# NeoSevenSegment.net
KiCad netlist of a schematic drawn in EAGLE
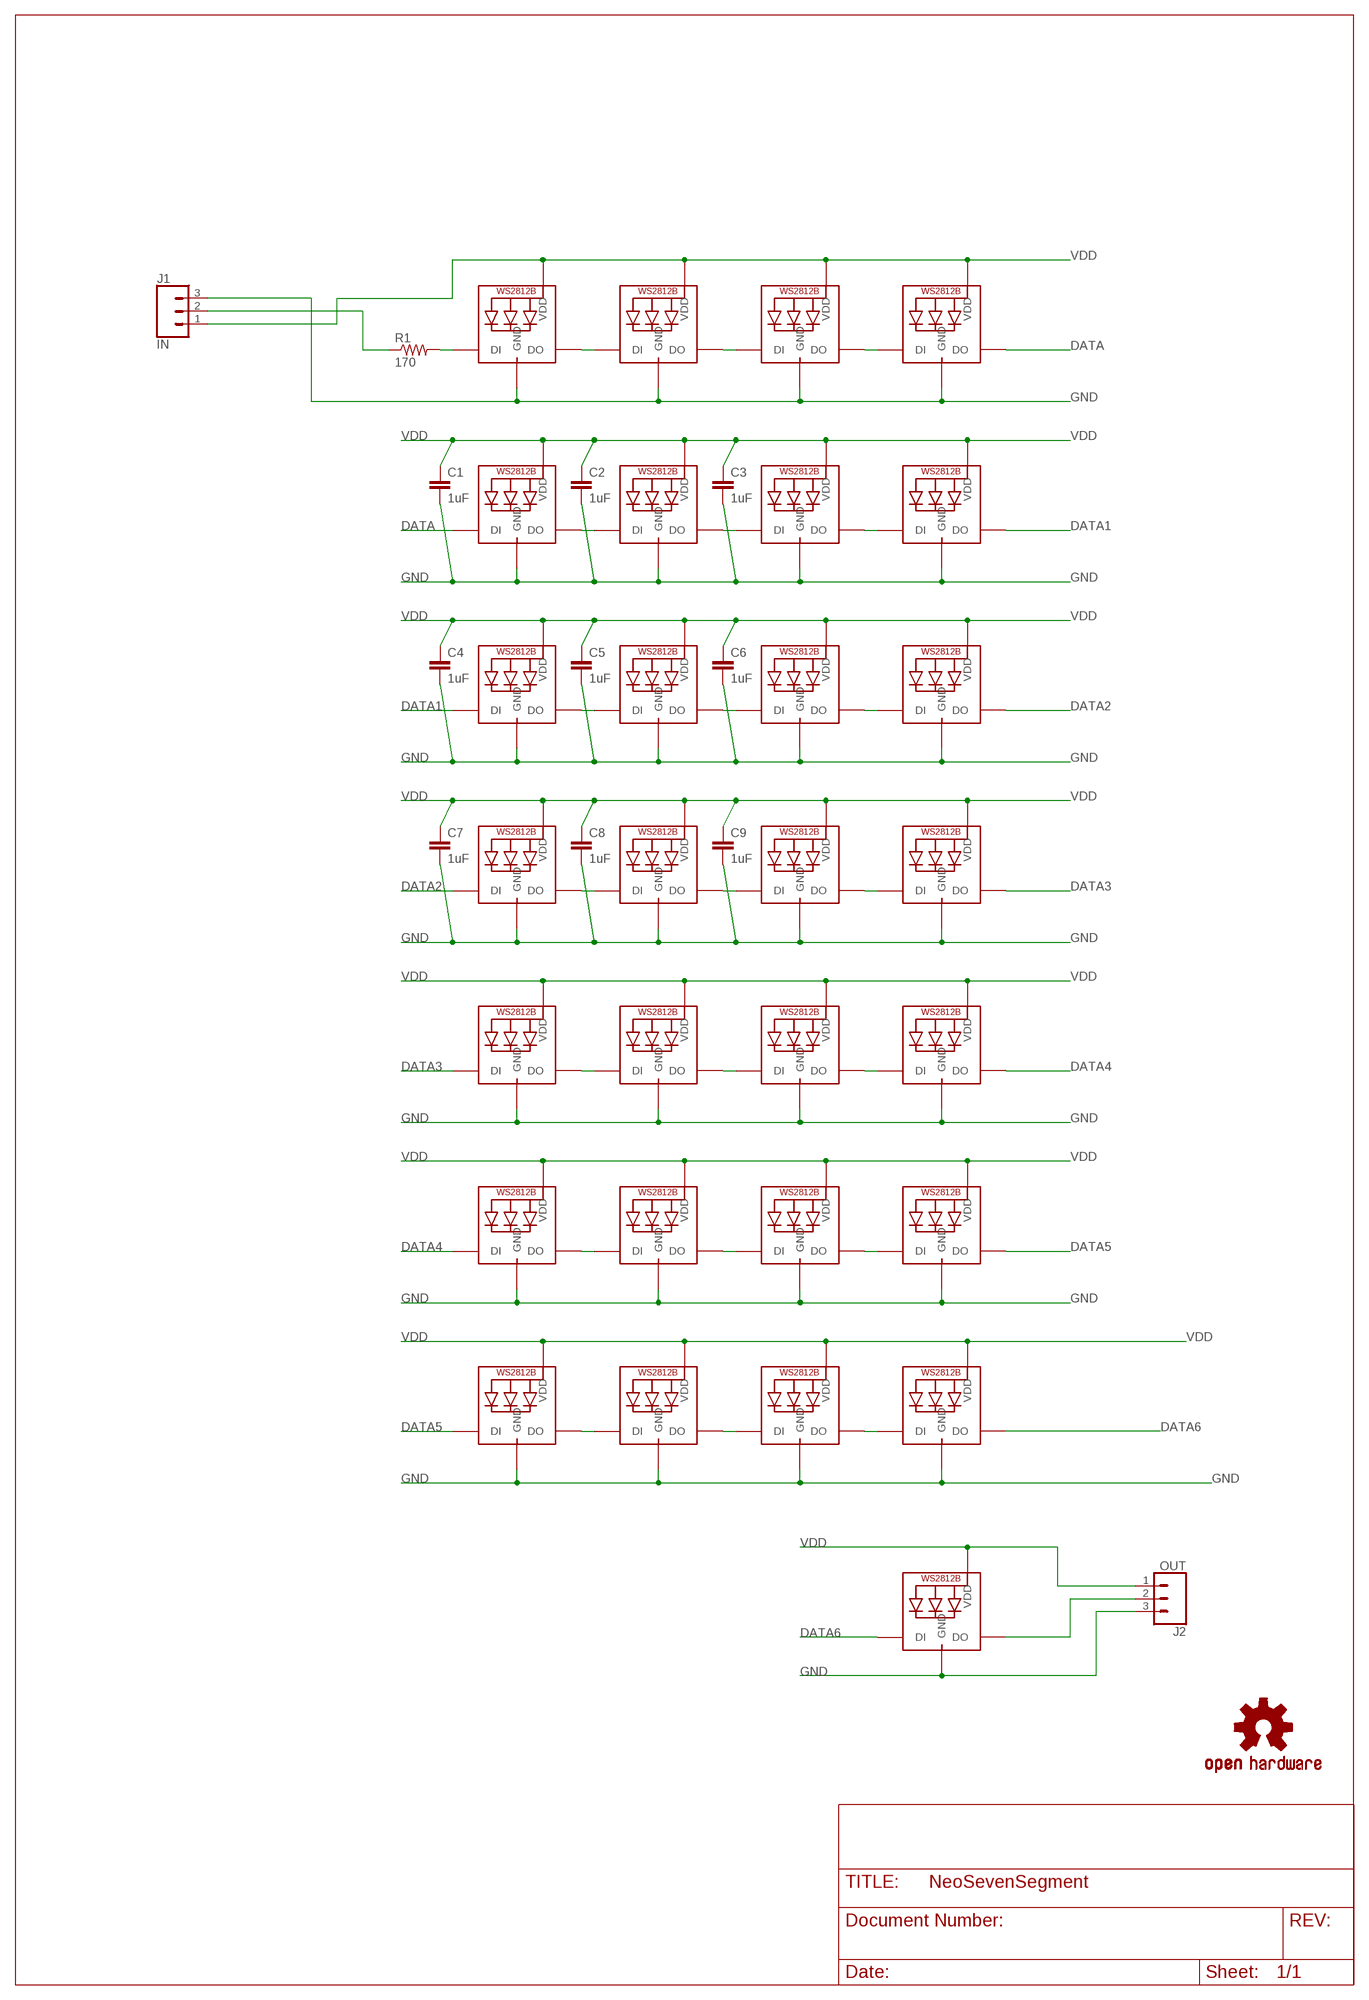
[diagram p0: schematic, sheet 1]

(export (version "E")
  (design (tool "Eeschema 10.0.6"))
  (components
    (comp (ref "C1")
      (value "1uF")
      (footprint "eagle-import:C0805")
      (libsource (lib "eagle-import") (part "C-EUC0805"))
    )
    (comp (ref "C2")
      (value "1uF")
      (footprint "eagle-import:C0805")
      (libsource (lib "eagle-import") (part "C-EUC0805"))
    )
    (comp (ref "C3")
      (value "1uF")
      (footprint "eagle-import:C0805")
      (libsource (lib "eagle-import") (part "C-EUC0805"))
    )
    (comp (ref "C4")
      (value "1uF")
      (footprint "eagle-import:C0805")
      (libsource (lib "eagle-import") (part "C-EUC0805"))
    )
    (comp (ref "C5")
      (value "1uF")
      (footprint "eagle-import:C0805")
      (libsource (lib "eagle-import") (part "C-EUC0805"))
    )
    (comp (ref "C6")
      (value "1uF")
      (footprint "eagle-import:C0805")
      (libsource (lib "eagle-import") (part "C-EUC0805"))
    )
    (comp (ref "C7")
      (value "1uF")
      (footprint "eagle-import:C0805")
      (libsource (lib "eagle-import") (part "C-EUC0805"))
    )
    (comp (ref "C8")
      (value "1uF")
      (footprint "eagle-import:C0805")
      (libsource (lib "eagle-import") (part "C-EUC0805"))
    )
    (comp (ref "C9")
      (value "1uF")
      (footprint "eagle-import:C0805")
      (libsource (lib "eagle-import") (part "C-EUC0805"))
    )
    (comp (ref "J1")
      (value "IN")
      (footprint "eagle-import:1X03_LONGPADS")
      (libsource (lib "eagle-import") (part "CONN_03LONGPADS"))
    )
    (comp (ref "J2")
      (value "OUT")
      (footprint "eagle-import:1X03_LONGPADS")
      (libsource (lib "eagle-import") (part "CONN_03LONGPADS"))
    )
    (comp (ref "LED1")
      (value "WS2812B_5050N")
      (footprint "eagle-import:WS2812B-NARROW")
      (libsource (lib "eagle-import") (part "WS2812B_5050N"))
    )
    (comp (ref "LED2")
      (value "WS2812B_5050N")
      (footprint "eagle-import:WS2812B-NARROW")
      (libsource (lib "eagle-import") (part "WS2812B_5050N"))
    )
    (comp (ref "LED3")
      (value "WS2812B_5050N")
      (footprint "eagle-import:WS2812B-NARROW")
      (libsource (lib "eagle-import") (part "WS2812B_5050N"))
    )
    (comp (ref "LED4")
      (value "WS2812B_5050N")
      (footprint "eagle-import:WS2812B-NARROW")
      (libsource (lib "eagle-import") (part "WS2812B_5050N"))
    )
    (comp (ref "LED5")
      (value "WS2812B_5050N")
      (footprint "eagle-import:WS2812B-NARROW")
      (libsource (lib "eagle-import") (part "WS2812B_5050N"))
    )
    (comp (ref "LED6")
      (value "WS2812B_5050N")
      (footprint "eagle-import:WS2812B-NARROW")
      (libsource (lib "eagle-import") (part "WS2812B_5050N"))
    )
    (comp (ref "LED7")
      (value "WS2812B_5050N")
      (footprint "eagle-import:WS2812B-NARROW")
      (libsource (lib "eagle-import") (part "WS2812B_5050N"))
    )
    (comp (ref "LED8")
      (value "WS2812B_5050N")
      (footprint "eagle-import:WS2812B-NARROW")
      (libsource (lib "eagle-import") (part "WS2812B_5050N"))
    )
    (comp (ref "LED9")
      (value "WS2812B_5050N")
      (footprint "eagle-import:WS2812B-NARROW")
      (libsource (lib "eagle-import") (part "WS2812B_5050N"))
    )
    (comp (ref "LED10")
      (value "WS2812B_5050N")
      (footprint "eagle-import:WS2812B-NARROW")
      (libsource (lib "eagle-import") (part "WS2812B_5050N"))
    )
    (comp (ref "LED11")
      (value "WS2812B_5050N")
      (footprint "eagle-import:WS2812B-NARROW")
      (libsource (lib "eagle-import") (part "WS2812B_5050N"))
    )
    (comp (ref "LED12")
      (value "WS2812B_5050N")
      (footprint "eagle-import:WS2812B-NARROW")
      (libsource (lib "eagle-import") (part "WS2812B_5050N"))
    )
    (comp (ref "LED13")
      (value "WS2812B_5050N")
      (footprint "eagle-import:WS2812B-NARROW")
      (libsource (lib "eagle-import") (part "WS2812B_5050N"))
    )
    (comp (ref "LED14")
      (value "WS2812B_5050N")
      (footprint "eagle-import:WS2812B-NARROW")
      (libsource (lib "eagle-import") (part "WS2812B_5050N"))
    )
    (comp (ref "LED15")
      (value "WS2812B_5050N")
      (footprint "eagle-import:WS2812B-NARROW")
      (libsource (lib "eagle-import") (part "WS2812B_5050N"))
    )
    (comp (ref "LED16")
      (value "WS2812B_5050N")
      (footprint "eagle-import:WS2812B-NARROW")
      (libsource (lib "eagle-import") (part "WS2812B_5050N"))
    )
    (comp (ref "LED17")
      (value "WS2812B_5050N")
      (footprint "eagle-import:WS2812B-NARROW")
      (libsource (lib "eagle-import") (part "WS2812B_5050N"))
    )
    (comp (ref "LED18")
      (value "WS2812B_5050N")
      (footprint "eagle-import:WS2812B-NARROW")
      (libsource (lib "eagle-import") (part "WS2812B_5050N"))
    )
    (comp (ref "LED19")
      (value "WS2812B_5050N")
      (footprint "eagle-import:WS2812B-NARROW")
      (libsource (lib "eagle-import") (part "WS2812B_5050N"))
    )
    (comp (ref "LED20")
      (value "WS2812B_5050N")
      (footprint "eagle-import:WS2812B-NARROW")
      (libsource (lib "eagle-import") (part "WS2812B_5050N"))
    )
    (comp (ref "LED21")
      (value "WS2812B_5050N")
      (footprint "eagle-import:WS2812B-NARROW")
      (libsource (lib "eagle-import") (part "WS2812B_5050N"))
    )
    (comp (ref "LED22")
      (value "WS2812B_5050N")
      (footprint "eagle-import:WS2812B-NARROW")
      (libsource (lib "eagle-import") (part "WS2812B_5050N"))
    )
    (comp (ref "LED23")
      (value "WS2812B_5050N")
      (footprint "eagle-import:WS2812B-NARROW")
      (libsource (lib "eagle-import") (part "WS2812B_5050N"))
    )
    (comp (ref "LED24")
      (value "WS2812B_5050N")
      (footprint "eagle-import:WS2812B-NARROW")
      (libsource (lib "eagle-import") (part "WS2812B_5050N"))
    )
    (comp (ref "LED25")
      (value "WS2812B_5050N")
      (footprint "eagle-import:WS2812B-NARROW")
      (libsource (lib "eagle-import") (part "WS2812B_5050N"))
    )
    (comp (ref "LED26")
      (value "WS2812B_5050N")
      (footprint "eagle-import:WS2812B-NARROW")
      (libsource (lib "eagle-import") (part "WS2812B_5050N"))
    )
    (comp (ref "LED27")
      (value "WS2812B_5050N")
      (footprint "eagle-import:WS2812B-NARROW")
      (libsource (lib "eagle-import") (part "WS2812B_5050N"))
    )
    (comp (ref "LED28")
      (value "WS2812B_5050N")
      (footprint "eagle-import:WS2812B-NARROW")
      (libsource (lib "eagle-import") (part "WS2812B_5050N"))
    )
    (comp (ref "LED29")
      (value "RGB 3535")
      (footprint "eagle-import:LED3535")
      (libsource (lib "eagle-import") (part "WS2812B3535"))
    )
    (comp (ref "LOGO1")
      (value "OSHW-LOGOM")
      (footprint "eagle-import:OSHW-LOGO-M")
      (libsource (lib "eagle-import") (part "OSHW-LOGOM"))
    )
    (comp (ref "R1")
      (value "170")
      (footprint "eagle-import:R0805")
      (libsource (lib "eagle-import") (part "R-US_R0805"))
    )
  )
  (nets
    (net (code "1") (name "/DATA") (class "Default")
      (node (ref "LED4") (pin "2-DOUT") (pinfunction "DO_2-DOUT") (pintype "output"))
      (node (ref "LED5") (pin "4-DIN") (pinfunction "DI_4-DIN") (pintype "input"))
    )
    (net (code "2") (name "/DATA1") (class "Default")
      (node (ref "LED8") (pin "2-DOUT") (pinfunction "DO_2-DOUT") (pintype "output"))
      (node (ref "LED9") (pin "4-DIN") (pinfunction "DI_4-DIN") (pintype "input"))
    )
    (net (code "3") (name "/DATA2") (class "Default")
      (node (ref "LED12") (pin "2-DOUT") (pinfunction "DO_2-DOUT") (pintype "output"))
      (node (ref "LED13") (pin "4-DIN") (pinfunction "DI_4-DIN") (pintype "input"))
    )
    (net (code "4") (name "/DATA3") (class "Default")
      (node (ref "LED16") (pin "2-DOUT") (pinfunction "DO_2-DOUT") (pintype "output"))
      (node (ref "LED17") (pin "4-DIN") (pinfunction "DI_4-DIN") (pintype "input"))
    )
    (net (code "5") (name "/DATA4") (class "Default")
      (node (ref "LED20") (pin "2-DOUT") (pinfunction "DO_2-DOUT") (pintype "output"))
      (node (ref "LED21") (pin "4-DIN") (pinfunction "DI_4-DIN") (pintype "input"))
    )
    (net (code "6") (name "/DATA5") (class "Default")
      (node (ref "LED24") (pin "2-DOUT") (pinfunction "DO_2-DOUT") (pintype "output"))
      (node (ref "LED25") (pin "4-DIN") (pinfunction "DI_4-DIN") (pintype "input"))
    )
    (net (code "7") (name "/DATA6") (class "Default")
      (node (ref "LED28") (pin "2-DOUT") (pinfunction "DO_2-DOUT") (pintype "output"))
      (node (ref "LED29") (pin "1") (pinfunction "DI_1") (pintype "input"))
    )
    (net (code "8") (name "/GND") (class "Default")
      (node (ref "C1") (pin "2") (pinfunction "2_2") (pintype "passive"))
      (node (ref "C2") (pin "2") (pinfunction "2_2") (pintype "passive"))
      (node (ref "C3") (pin "2") (pinfunction "2_2") (pintype "passive"))
      (node (ref "C4") (pin "2") (pinfunction "2_2") (pintype "passive"))
      (node (ref "C5") (pin "2") (pinfunction "2_2") (pintype "passive"))
      (node (ref "C6") (pin "2") (pinfunction "2_2") (pintype "passive"))
      (node (ref "C7") (pin "2") (pinfunction "2_2") (pintype "passive"))
      (node (ref "C8") (pin "2") (pinfunction "2_2") (pintype "passive"))
      (node (ref "C9") (pin "2") (pinfunction "2_2") (pintype "passive"))
      (node (ref "J1") (pin "3") (pinfunction "3_3") (pintype "passive"))
      (node (ref "J2") (pin "3") (pinfunction "3_3") (pintype "passive"))
      (node (ref "LED1") (pin "3-GND") (pinfunction "GND_3-GND") (pintype "power_in"))
      (node (ref "LED10") (pin "3-GND") (pinfunction "GND_3-GND") (pintype "power_in"))
      (node (ref "LED11") (pin "3-GND") (pinfunction "GND_3-GND") (pintype "power_in"))
      (node (ref "LED12") (pin "3-GND") (pinfunction "GND_3-GND") (pintype "power_in"))
      (node (ref "LED13") (pin "3-GND") (pinfunction "GND_3-GND") (pintype "power_in"))
      (node (ref "LED14") (pin "3-GND") (pinfunction "GND_3-GND") (pintype "power_in"))
      (node (ref "LED15") (pin "3-GND") (pinfunction "GND_3-GND") (pintype "power_in"))
      (node (ref "LED16") (pin "3-GND") (pinfunction "GND_3-GND") (pintype "power_in"))
      (node (ref "LED17") (pin "3-GND") (pinfunction "GND_3-GND") (pintype "power_in"))
      (node (ref "LED18") (pin "3-GND") (pinfunction "GND_3-GND") (pintype "power_in"))
      (node (ref "LED19") (pin "3-GND") (pinfunction "GND_3-GND") (pintype "power_in"))
      (node (ref "LED2") (pin "3-GND") (pinfunction "GND_3-GND") (pintype "power_in"))
      (node (ref "LED20") (pin "3-GND") (pinfunction "GND_3-GND") (pintype "power_in"))
      (node (ref "LED21") (pin "3-GND") (pinfunction "GND_3-GND") (pintype "power_in"))
      (node (ref "LED22") (pin "3-GND") (pinfunction "GND_3-GND") (pintype "power_in"))
      (node (ref "LED23") (pin "3-GND") (pinfunction "GND_3-GND") (pintype "power_in"))
      (node (ref "LED24") (pin "3-GND") (pinfunction "GND_3-GND") (pintype "power_in"))
      (node (ref "LED25") (pin "3-GND") (pinfunction "GND_3-GND") (pintype "power_in"))
      (node (ref "LED26") (pin "3-GND") (pinfunction "GND_3-GND") (pintype "power_in"))
      (node (ref "LED27") (pin "3-GND") (pinfunction "GND_3-GND") (pintype "power_in"))
      (node (ref "LED28") (pin "3-GND") (pinfunction "GND_3-GND") (pintype "power_in"))
      (node (ref "LED29") (pin "4") (pinfunction "GND_4") (pintype "power_in"))
      (node (ref "LED3") (pin "3-GND") (pinfunction "GND_3-GND") (pintype "power_in"))
      (node (ref "LED4") (pin "3-GND") (pinfunction "GND_3-GND") (pintype "power_in"))
      (node (ref "LED5") (pin "3-GND") (pinfunction "GND_3-GND") (pintype "power_in"))
      (node (ref "LED6") (pin "3-GND") (pinfunction "GND_3-GND") (pintype "power_in"))
      (node (ref "LED7") (pin "3-GND") (pinfunction "GND_3-GND") (pintype "power_in"))
      (node (ref "LED8") (pin "3-GND") (pinfunction "GND_3-GND") (pintype "power_in"))
      (node (ref "LED9") (pin "3-GND") (pinfunction "GND_3-GND") (pintype "power_in"))
    )
    (net (code "9") (name "/VDD") (class "Default")
      (node (ref "C1") (pin "1") (pinfunction "1_1") (pintype "passive"))
      (node (ref "C2") (pin "1") (pinfunction "1_1") (pintype "passive"))
      (node (ref "C3") (pin "1") (pinfunction "1_1") (pintype "passive"))
      (node (ref "C4") (pin "1") (pinfunction "1_1") (pintype "passive"))
      (node (ref "C5") (pin "1") (pinfunction "1_1") (pintype "passive"))
      (node (ref "C6") (pin "1") (pinfunction "1_1") (pintype "passive"))
      (node (ref "C7") (pin "1") (pinfunction "1_1") (pintype "passive"))
      (node (ref "C8") (pin "1") (pinfunction "1_1") (pintype "passive"))
      (node (ref "C9") (pin "1") (pinfunction "1_1") (pintype "passive"))
      (node (ref "J1") (pin "1") (pinfunction "1_1") (pintype "passive"))
      (node (ref "J2") (pin "1") (pinfunction "1_1") (pintype "passive"))
      (node (ref "LED1") (pin "1-VDD") (pinfunction "VDD_1-VDD") (pintype "power_in"))
      (node (ref "LED10") (pin "1-VDD") (pinfunction "VDD_1-VDD") (pintype "power_in"))
      (node (ref "LED11") (pin "1-VDD") (pinfunction "VDD_1-VDD") (pintype "power_in"))
      (node (ref "LED12") (pin "1-VDD") (pinfunction "VDD_1-VDD") (pintype "power_in"))
      (node (ref "LED13") (pin "1-VDD") (pinfunction "VDD_1-VDD") (pintype "power_in"))
      (node (ref "LED14") (pin "1-VDD") (pinfunction "VDD_1-VDD") (pintype "power_in"))
      (node (ref "LED15") (pin "1-VDD") (pinfunction "VDD_1-VDD") (pintype "power_in"))
      (node (ref "LED16") (pin "1-VDD") (pinfunction "VDD_1-VDD") (pintype "power_in"))
      (node (ref "LED17") (pin "1-VDD") (pinfunction "VDD_1-VDD") (pintype "power_in"))
      (node (ref "LED18") (pin "1-VDD") (pinfunction "VDD_1-VDD") (pintype "power_in"))
      (node (ref "LED19") (pin "1-VDD") (pinfunction "VDD_1-VDD") (pintype "power_in"))
      (node (ref "LED2") (pin "1-VDD") (pinfunction "VDD_1-VDD") (pintype "power_in"))
      (node (ref "LED20") (pin "1-VDD") (pinfunction "VDD_1-VDD") (pintype "power_in"))
      (node (ref "LED21") (pin "1-VDD") (pinfunction "VDD_1-VDD") (pintype "power_in"))
      (node (ref "LED22") (pin "1-VDD") (pinfunction "VDD_1-VDD") (pintype "power_in"))
      (node (ref "LED23") (pin "1-VDD") (pinfunction "VDD_1-VDD") (pintype "power_in"))
      (node (ref "LED24") (pin "1-VDD") (pinfunction "VDD_1-VDD") (pintype "power_in"))
      (node (ref "LED25") (pin "1-VDD") (pinfunction "VDD_1-VDD") (pintype "power_in"))
      (node (ref "LED26") (pin "1-VDD") (pinfunction "VDD_1-VDD") (pintype "power_in"))
      (node (ref "LED27") (pin "1-VDD") (pinfunction "VDD_1-VDD") (pintype "power_in"))
      (node (ref "LED28") (pin "1-VDD") (pinfunction "VDD_1-VDD") (pintype "power_in"))
      (node (ref "LED29") (pin "2") (pinfunction "VDD_2") (pintype "power_in"))
      (node (ref "LED3") (pin "1-VDD") (pinfunction "VDD_1-VDD") (pintype "power_in"))
      (node (ref "LED4") (pin "1-VDD") (pinfunction "VDD_1-VDD") (pintype "power_in"))
      (node (ref "LED5") (pin "1-VDD") (pinfunction "VDD_1-VDD") (pintype "power_in"))
      (node (ref "LED6") (pin "1-VDD") (pinfunction "VDD_1-VDD") (pintype "power_in"))
      (node (ref "LED7") (pin "1-VDD") (pinfunction "VDD_1-VDD") (pintype "power_in"))
      (node (ref "LED8") (pin "1-VDD") (pinfunction "VDD_1-VDD") (pintype "power_in"))
      (node (ref "LED9") (pin "1-VDD") (pinfunction "VDD_1-VDD") (pintype "power_in"))
    )
    (net (code "10") (name "Net-(J1-Pad2)") (class "Default")
      (node (ref "J1") (pin "2") (pinfunction "2_2") (pintype "passive"))
      (node (ref "R1") (pin "1") (pinfunction "1_1") (pintype "passive"))
    )
    (net (code "11") (name "Net-(LED1-DI)") (class "Default")
      (node (ref "LED1") (pin "4-DIN") (pinfunction "DI_4-DIN") (pintype "input"))
      (node (ref "R1") (pin "2") (pinfunction "2_2") (pintype "passive"))
    )
    (net (code "12") (name "Net-(LED1-DO)") (class "Default")
      (node (ref "LED1") (pin "2-DOUT") (pinfunction "DO_2-DOUT") (pintype "output"))
      (node (ref "LED2") (pin "4-DIN") (pinfunction "DI_4-DIN") (pintype "input"))
    )
    (net (code "13") (name "Net-(LED2-DO)") (class "Default")
      (node (ref "LED2") (pin "2-DOUT") (pinfunction "DO_2-DOUT") (pintype "output"))
      (node (ref "LED3") (pin "4-DIN") (pinfunction "DI_4-DIN") (pintype "input"))
    )
    (net (code "14") (name "Net-(LED3-DO)") (class "Default")
      (node (ref "LED3") (pin "2-DOUT") (pinfunction "DO_2-DOUT") (pintype "output"))
      (node (ref "LED4") (pin "4-DIN") (pinfunction "DI_4-DIN") (pintype "input"))
    )
    (net (code "15") (name "Net-(LED5-DO)") (class "Default")
      (node (ref "LED5") (pin "2-DOUT") (pinfunction "DO_2-DOUT") (pintype "output"))
      (node (ref "LED6") (pin "4-DIN") (pinfunction "DI_4-DIN") (pintype "input"))
    )
    (net (code "16") (name "Net-(LED6-DO)") (class "Default")
      (node (ref "LED6") (pin "2-DOUT") (pinfunction "DO_2-DOUT") (pintype "output"))
      (node (ref "LED7") (pin "4-DIN") (pinfunction "DI_4-DIN") (pintype "input"))
    )
    (net (code "17") (name "Net-(LED7-DO)") (class "Default")
      (node (ref "LED7") (pin "2-DOUT") (pinfunction "DO_2-DOUT") (pintype "output"))
      (node (ref "LED8") (pin "4-DIN") (pinfunction "DI_4-DIN") (pintype "input"))
    )
    (net (code "18") (name "Net-(LED10-DI)") (class "Default")
      (node (ref "LED10") (pin "4-DIN") (pinfunction "DI_4-DIN") (pintype "input"))
      (node (ref "LED9") (pin "2-DOUT") (pinfunction "DO_2-DOUT") (pintype "output"))
    )
    (net (code "19") (name "Net-(LED10-DO)") (class "Default")
      (node (ref "LED10") (pin "2-DOUT") (pinfunction "DO_2-DOUT") (pintype "output"))
      (node (ref "LED11") (pin "4-DIN") (pinfunction "DI_4-DIN") (pintype "input"))
    )
    (net (code "20") (name "Net-(LED11-DO)") (class "Default")
      (node (ref "LED11") (pin "2-DOUT") (pinfunction "DO_2-DOUT") (pintype "output"))
      (node (ref "LED12") (pin "4-DIN") (pinfunction "DI_4-DIN") (pintype "input"))
    )
    (net (code "21") (name "Net-(LED13-DO)") (class "Default")
      (node (ref "LED13") (pin "2-DOUT") (pinfunction "DO_2-DOUT") (pintype "output"))
      (node (ref "LED14") (pin "4-DIN") (pinfunction "DI_4-DIN") (pintype "input"))
    )
    (net (code "22") (name "Net-(LED14-DO)") (class "Default")
      (node (ref "LED14") (pin "2-DOUT") (pinfunction "DO_2-DOUT") (pintype "output"))
      (node (ref "LED15") (pin "4-DIN") (pinfunction "DI_4-DIN") (pintype "input"))
    )
    (net (code "23") (name "Net-(LED15-DO)") (class "Default")
      (node (ref "LED15") (pin "2-DOUT") (pinfunction "DO_2-DOUT") (pintype "output"))
      (node (ref "LED16") (pin "4-DIN") (pinfunction "DI_4-DIN") (pintype "input"))
    )
    (net (code "24") (name "Net-(LED17-DO)") (class "Default")
      (node (ref "LED17") (pin "2-DOUT") (pinfunction "DO_2-DOUT") (pintype "output"))
      (node (ref "LED18") (pin "4-DIN") (pinfunction "DI_4-DIN") (pintype "input"))
    )
    (net (code "25") (name "Net-(LED18-DO)") (class "Default")
      (node (ref "LED18") (pin "2-DOUT") (pinfunction "DO_2-DOUT") (pintype "output"))
      (node (ref "LED19") (pin "4-DIN") (pinfunction "DI_4-DIN") (pintype "input"))
    )
    (net (code "26") (name "Net-(LED19-DO)") (class "Default")
      (node (ref "LED19") (pin "2-DOUT") (pinfunction "DO_2-DOUT") (pintype "output"))
      (node (ref "LED20") (pin "4-DIN") (pinfunction "DI_4-DIN") (pintype "input"))
    )
    (net (code "27") (name "Net-(LED21-DO)") (class "Default")
      (node (ref "LED21") (pin "2-DOUT") (pinfunction "DO_2-DOUT") (pintype "output"))
      (node (ref "LED22") (pin "4-DIN") (pinfunction "DI_4-DIN") (pintype "input"))
    )
    (net (code "28") (name "Net-(LED22-DO)") (class "Default")
      (node (ref "LED22") (pin "2-DOUT") (pinfunction "DO_2-DOUT") (pintype "output"))
      (node (ref "LED23") (pin "4-DIN") (pinfunction "DI_4-DIN") (pintype "input"))
    )
    (net (code "29") (name "Net-(LED23-DO)") (class "Default")
      (node (ref "LED23") (pin "2-DOUT") (pinfunction "DO_2-DOUT") (pintype "output"))
      (node (ref "LED24") (pin "4-DIN") (pinfunction "DI_4-DIN") (pintype "input"))
    )
    (net (code "30") (name "Net-(LED25-DO)") (class "Default")
      (node (ref "LED25") (pin "2-DOUT") (pinfunction "DO_2-DOUT") (pintype "output"))
      (node (ref "LED26") (pin "4-DIN") (pinfunction "DI_4-DIN") (pintype "input"))
    )
    (net (code "31") (name "Net-(LED26-DO)") (class "Default")
      (node (ref "LED26") (pin "2-DOUT") (pinfunction "DO_2-DOUT") (pintype "output"))
      (node (ref "LED27") (pin "4-DIN") (pinfunction "DI_4-DIN") (pintype "input"))
    )
    (net (code "32") (name "Net-(LED27-DO)") (class "Default")
      (node (ref "LED27") (pin "2-DOUT") (pinfunction "DO_2-DOUT") (pintype "output"))
      (node (ref "LED28") (pin "4-DIN") (pinfunction "DI_4-DIN") (pintype "input"))
    )
    (net (code "33") (name "Net-(LED29-DO)") (class "Default")
      (node (ref "J2") (pin "2") (pinfunction "2_2") (pintype "passive"))
      (node (ref "LED29") (pin "3") (pinfunction "DO_3") (pintype "output"))
    )
  )
)
